# 15-DistanceSRF05.net
KiCad netlist of a schematic drawn in Altium Designer
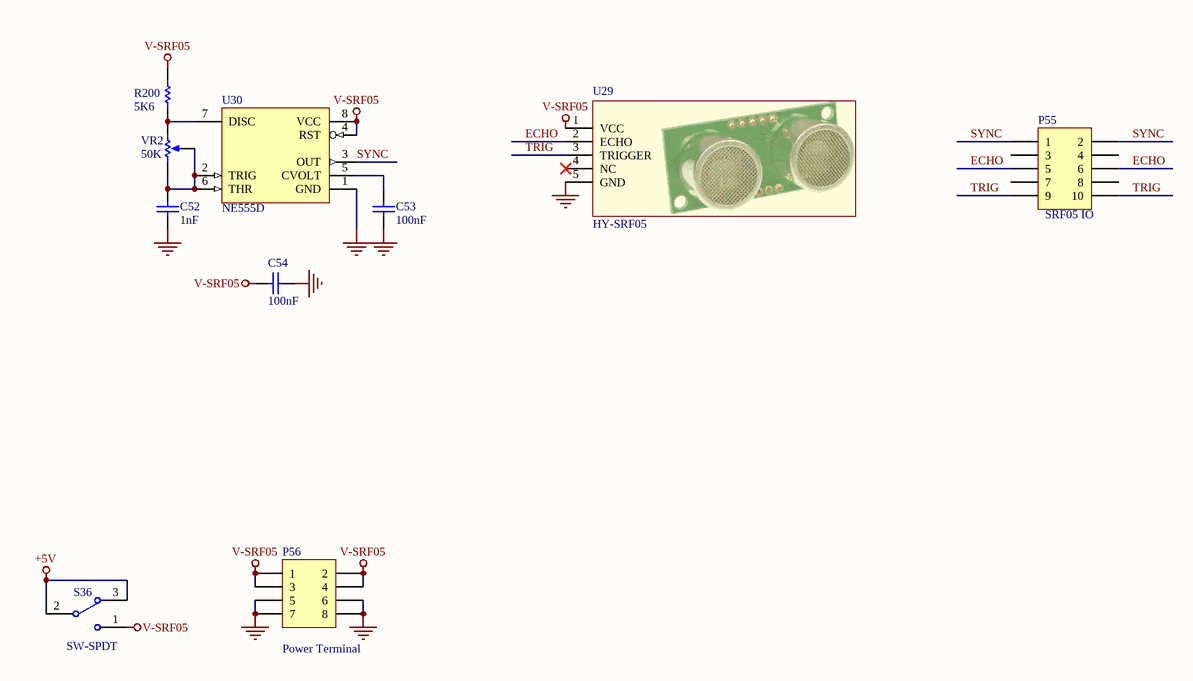
[diagram p0: 15-DistanceSRF05.SchDoc]

(export (version "E")
  (design (tool "Eeschema 10.0.6"))
  (components
    (comp (ref "C52")
      (value "1nF")
      (footprint "c-0805")
      (description "Capacitor")
      (fields (field (name "Comment") "102") (field (name "PUBLISHER") "Altium Limited"))
      (libsource (lib "Miscellaneous Devices") (part "Cap"))
    )
    (comp (ref "C53")
      (value "100nF")
      (footprint "c-0805")
      (description "Capacitor")
      (fields (field (name "Comment") "104") (field (name "PUBLISHER") "Altium Limited"))
      (libsource (lib "Miscellaneous Devices") (part "Cap"))
    )
    (comp (ref "C54")
      (value "100nF")
      (footprint "c-0805")
      (description "Capacitor")
      (fields (field (name "Comment") "104") (field (name "PUBLISHER") "Altium Limited"))
      (libsource (lib "Miscellaneous Devices") (part "Cap"))
    )
    (comp (ref "P55")
      (value "SRF05 IO")
      (footprint "HDR2X5")
      (description "Header, 5-Pin, Dual row")
      (fields (field (name "Comment") "Header 5X2"))
      (libsource (lib "Miscellaneous Connectors") (part "Header 5X2"))
    )
    (comp (ref "P56")
      (value "Header 4X2")
      (footprint "HDR2X4")
      (description "Header, 4-Pin, Dual row")
      (fields (field (name "PUBLISHER") "Power Terminal"))
      (libsource (lib "Miscellaneous Connectors") (part "Header 4X2"))
    )
    (comp (ref "R200")
      (value "5K6")
      (footprint "R-0805")
      (description "Resistor")
      (fields (field (name "Comment") "562") (field (name "PUBLISHER") "Altium Limited"))
      (libsource (lib "Miscellaneous Devices") (part "Res1"))
    )
    (comp (ref "S36")
      (value "SW-SPDT")
      (footprint "SW-DIP1SMD")
      (description "SPDT Subminiature Toggle Switch, Right Angle Mounting, Vertical Actuation")
      (fields (field (name "PUBLISHER") "Altium Limited"))
      (libsource (lib "Miscellaneous Devices") (part "SW-SPDT"))
    )
    (comp (ref "U29") (value "HY-SRF05") (footprint "SRF-05") (libsource (lib "nhoccon1") (part "HY-SRF05")))
    (comp (ref "U30")
      (value "NE555D")
      (footprint "DIP8")
      (description "General-Purpose Single Bipolar Timer")
      (fields (field (name "PUBLISHER") "Altium Limited"))
      (libsource (lib "ST Analog Timer Circuit") (part "NE555D"))
    )
    (comp (ref "VR2")
      (value "50K")
      (footprint "VR1")
      (description "Potentiometer")
      (fields (field (name "PUBLISHER") "Altium Limited"))
      (libsource (lib "Miscellaneous Devices") (part "RPot"))
    )
  )
  (nets
    (net (code "1") (name "+5V") (class "Default")
      (node (ref "S36") (pin "2") (pinfunction "2_2") (pintype "passive"))
      (node (ref "S36") (pin "3") (pinfunction "3_3") (pintype "passive"))
    )
    (net (code "2") (name "/ECHO") (class "Default")
      (node (ref "P55") (pin "5") (pinfunction "5_5") (pintype "passive"))
      (node (ref "P55") (pin "6") (pinfunction "6_6") (pintype "passive"))
      (node (ref "U29") (pin "2") (pinfunction "ECHO_2") (pintype "passive"))
    )
    (net (code "3") (name "/SYNC") (class "Default")
      (node (ref "P55") (pin "1") (pinfunction "1_1") (pintype "passive"))
      (node (ref "P55") (pin "2") (pinfunction "2_2") (pintype "passive"))
      (node (ref "U30") (pin "3") (pinfunction "OUT_3") (pintype "output"))
    )
    (net (code "4") (name "/TRIG") (class "Default")
      (node (ref "P55") (pin "10") (pinfunction "10_10") (pintype "passive"))
      (node (ref "P55") (pin "9") (pinfunction "9_9") (pintype "passive"))
      (node (ref "U29") (pin "3") (pinfunction "TRIGGER_3") (pintype "passive"))
    )
    (net (code "5") (name "GND") (class "Default")
      (node (ref "C52") (pin "1") (pinfunction "1_1") (pintype "passive"))
      (node (ref "C53") (pin "1") (pinfunction "1_1") (pintype "passive"))
      (node (ref "C54") (pin "1") (pinfunction "1_1") (pintype "passive"))
      (node (ref "P56") (pin "5") (pinfunction "5_5") (pintype "passive"))
      (node (ref "P56") (pin "6") (pinfunction "6_6") (pintype "passive"))
      (node (ref "P56") (pin "7") (pinfunction "7_7") (pintype "passive"))
      (node (ref "P56") (pin "8") (pinfunction "8_8") (pintype "passive"))
      (node (ref "U29") (pin "5") (pinfunction "GND_5") (pintype "passive"))
      (node (ref "U30") (pin "1") (pinfunction "GND_1") (pintype "power_in"))
    )
    (net (code "6") (name "Net-(U30-CVOLT)") (class "Default")
      (node (ref "C53") (pin "2") (pinfunction "2_2") (pintype "passive"))
      (node (ref "U30") (pin "5") (pinfunction "CVOLT_5") (pintype "passive"))
    )
    (net (code "7") (name "Net-(U30-DISC)") (class "Default")
      (node (ref "R200") (pin "1") (pinfunction "1_1") (pintype "passive"))
      (node (ref "U30") (pin "7") (pinfunction "DISC_7") (pintype "open_collector"))
      (node (ref "VR2") (pin "3") (pinfunction "BOT_3") (pintype "passive"))
    )
    (net (code "8") (name "Net-(U30-THR)") (class "Default")
      (node (ref "C52") (pin "2") (pinfunction "2_2") (pintype "passive"))
      (node (ref "U30") (pin "2") (pinfunction "TRIG_2") (pintype "input"))
      (node (ref "U30") (pin "6") (pinfunction "THR_6") (pintype "input"))
      (node (ref "VR2") (pin "1") (pinfunction "TOP_1") (pintype "passive"))
      (node (ref "VR2") (pin "2") (pinfunction "TAP_2") (pintype "passive"))
    )
    (net (code "9") (name "V-SRF05") (class "Default")
      (node (ref "C54") (pin "2") (pinfunction "2_2") (pintype "passive"))
      (node (ref "P56") (pin "1") (pinfunction "1_1") (pintype "passive"))
      (node (ref "P56") (pin "2") (pinfunction "2_2") (pintype "passive"))
      (node (ref "P56") (pin "3") (pinfunction "3_3") (pintype "passive"))
      (node (ref "P56") (pin "4") (pinfunction "4_4") (pintype "passive"))
      (node (ref "R200") (pin "2") (pinfunction "2_2") (pintype "passive"))
      (node (ref "S36") (pin "1") (pinfunction "1_1") (pintype "passive"))
      (node (ref "U29") (pin "1") (pinfunction "VCC_1") (pintype "passive"))
      (node (ref "U30") (pin "4") (pinfunction "RST_4") (pintype "input"))
      (node (ref "U30") (pin "8") (pinfunction "VCC_8") (pintype "power_in"))
    )
    (net (code "10") (name "unconnected-(P55-Pad3)") (class "Default")
      (node (ref "P55") (pin "3") (pinfunction "3_3") (pintype "passive"))
    )
    (net (code "11") (name "unconnected-(P55-Pad4)") (class "Default")
      (node (ref "P55") (pin "4") (pinfunction "4_4") (pintype "passive"))
    )
    (net (code "12") (name "unconnected-(P55-Pad7)") (class "Default")
      (node (ref "P55") (pin "7") (pinfunction "7_7") (pintype "passive"))
    )
    (net (code "13") (name "unconnected-(P55-Pad8)") (class "Default")
      (node (ref "P55") (pin "8") (pinfunction "8_8") (pintype "passive"))
    )
    (net (code "14") (name "unconnected-(U29-NC-Pad4)") (class "Default")
      (node (ref "U29") (pin "4") (pinfunction "NC_4") (pintype "passive+no_connect"))
    )
  )
)
